# main.net
KiCad netlist of a schematic drawn in EAGLE
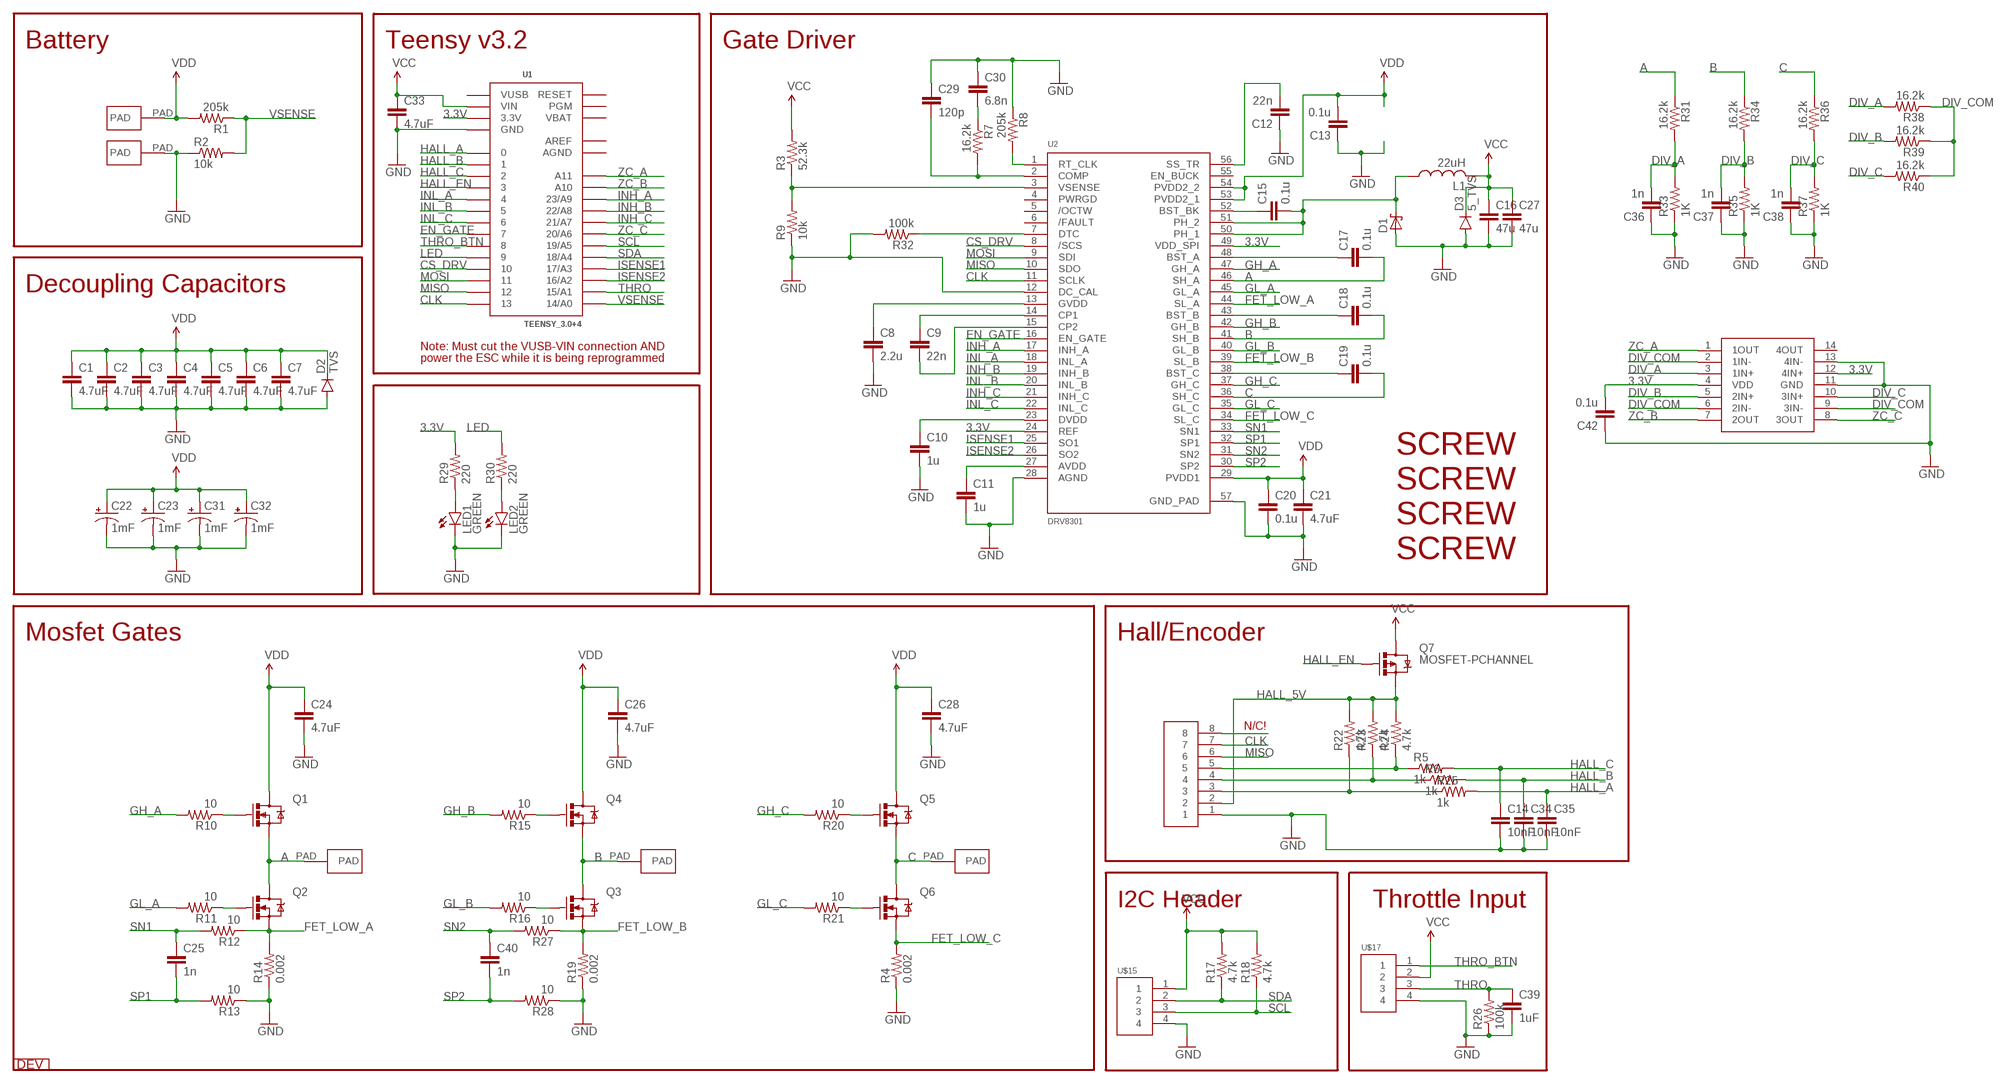
[diagram p0: schematic, sheet 1]

(export (version "E")
  (design (tool "Eeschema 10.0.6"))
  (components
    (comp (ref "C1")
      (value "4.7uF")
      (footprint "eagle-import:1206")
      (libsource (lib "eagle-import") (part "CAP1206"))
    )
    (comp (ref "C2")
      (value "4.7uF")
      (footprint "eagle-import:1206")
      (libsource (lib "eagle-import") (part "CAP1206"))
    )
    (comp (ref "C3")
      (value "4.7uF")
      (footprint "eagle-import:1206")
      (libsource (lib "eagle-import") (part "CAP1206"))
    )
    (comp (ref "C4")
      (value "4.7uF")
      (footprint "eagle-import:1206")
      (libsource (lib "eagle-import") (part "CAP1206"))
    )
    (comp (ref "C5")
      (value "4.7uF")
      (footprint "eagle-import:1206")
      (libsource (lib "eagle-import") (part "CAP1206"))
    )
    (comp (ref "C6")
      (value "4.7uF")
      (footprint "eagle-import:1206")
      (libsource (lib "eagle-import") (part "CAP1206"))
    )
    (comp (ref "C7")
      (value "4.7uF")
      (footprint "eagle-import:1206")
      (libsource (lib "eagle-import") (part "CAP1206"))
    )
    (comp (ref "C8")
      (value "2.2u")
      (footprint "eagle-import:0603-CAP")
      (libsource (lib "eagle-import") (part "CAP0603-CAP"))
    )
    (comp (ref "C9")
      (value "22n")
      (footprint "eagle-import:0603-CAP")
      (libsource (lib "eagle-import") (part "CAP0603-CAP"))
    )
    (comp (ref "C10")
      (value "1u")
      (footprint "eagle-import:0603-CAP")
      (libsource (lib "eagle-import") (part "CAP0603-CAP"))
    )
    (comp (ref "C11")
      (value "1u")
      (footprint "eagle-import:0603-CAP")
      (libsource (lib "eagle-import") (part "CAP0603-CAP"))
    )
    (comp (ref "C12")
      (value "22n")
      (footprint "eagle-import:0603-CAP")
      (libsource (lib "eagle-import") (part "CAP0603-CAP"))
    )
    (comp (ref "C13")
      (value "0.1u")
      (footprint "eagle-import:0603-CAP")
      (libsource (lib "eagle-import") (part "CAP0603-CAP"))
    )
    (comp (ref "C14")
      (value "10nF")
      (footprint "eagle-import:0603-CAP")
      (libsource (lib "eagle-import") (part "SparkFun-Passives_CAP0603-CAP"))
    )
    (comp (ref "C15")
      (value "0.1u")
      (footprint "eagle-import:0603-CAP")
      (libsource (lib "eagle-import") (part "CAP0603-CAP"))
    )
    (comp (ref "C16")
      (value "47u")
      (footprint "eagle-import:0805")
      (libsource (lib "eagle-import") (part "CAP0805"))
    )
    (comp (ref "C17")
      (value "0.1u")
      (footprint "eagle-import:0603-CAP")
      (libsource (lib "eagle-import") (part "CAP0603-CAP"))
    )
    (comp (ref "C18")
      (value "0.1u")
      (footprint "eagle-import:0603-CAP")
      (libsource (lib "eagle-import") (part "CAP0603-CAP"))
    )
    (comp (ref "C19")
      (value "0.1u")
      (footprint "eagle-import:0603-CAP")
      (libsource (lib "eagle-import") (part "CAP0603-CAP"))
    )
    (comp (ref "C20")
      (value "0.1u")
      (footprint "eagle-import:0603-CAP")
      (libsource (lib "eagle-import") (part "CAP0603-CAP"))
    )
    (comp (ref "C21")
      (value "4.7uF")
      (footprint "eagle-import:1206")
      (libsource (lib "eagle-import") (part "CAP1206"))
    )
    (comp (ref "C22")
      (value "1mF")
      (footprint "eagle-import:CPOL-RADIAL-1000UF-25V")
      (libsource (lib "eagle-import") (part "CAP_POLPTH4"))
    )
    (comp (ref "C23")
      (value "1mF")
      (footprint "eagle-import:CPOL-RADIAL-1000UF-25V")
      (libsource (lib "eagle-import") (part "CAP_POLPTH4"))
    )
    (comp (ref "C24")
      (value "4.7uF")
      (footprint "eagle-import:1206")
      (libsource (lib "eagle-import") (part "CAP1206"))
    )
    (comp (ref "C25")
      (value "1n")
      (footprint "eagle-import:0603-CAP")
      (libsource (lib "eagle-import") (part "CAP0603-CAP"))
    )
    (comp (ref "C26")
      (value "4.7uF")
      (footprint "eagle-import:1206")
      (libsource (lib "eagle-import") (part "CAP1206"))
    )
    (comp (ref "C27")
      (value "47u")
      (footprint "eagle-import:0805")
      (libsource (lib "eagle-import") (part "CAP0805"))
    )
    (comp (ref "C28")
      (value "4.7uF")
      (footprint "eagle-import:1206")
      (libsource (lib "eagle-import") (part "CAP1206"))
    )
    (comp (ref "C29")
      (value "120p")
      (footprint "eagle-import:0603-CAP")
      (libsource (lib "eagle-import") (part "CAP0603-CAP"))
    )
    (comp (ref "C30")
      (value "6.8n")
      (footprint "eagle-import:0603-CAP")
      (libsource (lib "eagle-import") (part "CAP0603-CAP"))
    )
    (comp (ref "C31")
      (value "1mF")
      (footprint "eagle-import:CPOL-RADIAL-1000UF-25V")
      (libsource (lib "eagle-import") (part "CAP_POLPTH4"))
    )
    (comp (ref "C32")
      (value "1mF")
      (footprint "eagle-import:CPOL-RADIAL-1000UF-25V")
      (libsource (lib "eagle-import") (part "CAP_POLPTH4"))
    )
    (comp (ref "C33")
      (value "4.7uF")
      (footprint "eagle-import:1206")
      (libsource (lib "eagle-import") (part "CAP1206"))
    )
    (comp (ref "C34")
      (value "10nF")
      (footprint "eagle-import:0603-CAP")
      (libsource (lib "eagle-import") (part "SparkFun-Passives_CAP0603-CAP"))
    )
    (comp (ref "C35")
      (value "10nF")
      (footprint "eagle-import:0603-CAP")
      (libsource (lib "eagle-import") (part "SparkFun-Passives_CAP0603-CAP"))
    )
    (comp (ref "C36")
      (value "1n")
      (footprint "eagle-import:0603-CAP")
      (libsource (lib "eagle-import") (part "CAP0603-CAP"))
    )
    (comp (ref "C37")
      (value "1n")
      (footprint "eagle-import:0603-CAP")
      (libsource (lib "eagle-import") (part "CAP0603-CAP"))
    )
    (comp (ref "C38")
      (value "1n")
      (footprint "eagle-import:0603-CAP")
      (libsource (lib "eagle-import") (part "CAP0603-CAP"))
    )
    (comp (ref "C39")
      (value "1uF")
      (footprint "eagle-import:0603-CAP")
      (libsource (lib "eagle-import") (part "SparkFun-Passives_CAP0603-CAP"))
    )
    (comp (ref "C40")
      (value "1n")
      (footprint "eagle-import:0603-CAP")
      (libsource (lib "eagle-import") (part "CAP0603-CAP"))
    )
    (comp (ref "C42")
      (value "0.1u")
      (footprint "eagle-import:0603-CAP")
      (libsource (lib "eagle-import") (part "CAP0603-CAP"))
    )
    (comp (ref "D1")
      (value "SCHOTTKY_SMA")
      (footprint "eagle-import:SMA")
      (libsource (lib "eagle-import") (part "SCHOTTKY_SMA"))
    )
    (comp (ref "D2")
      (value "TVS")
      (footprint "eagle-import:SMC")
      (libsource (lib "eagle-import") (part "DIODEES3J"))
    )
    (comp (ref "D3")
      (value "5_TVS")
      (footprint "eagle-import:SOT23-3")
      (libsource (lib "eagle-import") (part "DIODESOT23"))
    )
    (comp (ref "L1")
      (value "22uH")
      (footprint "eagle-import:L5650M")
      (libsource (lib "eagle-import") (part "L-USL5650M"))
    )
    (comp (ref "LED1")
      (value "GREEN")
      (footprint "eagle-import:LED-1206")
      (libsource (lib "eagle-import") (part "LED1206"))
    )
    (comp (ref "LED2")
      (value "GREEN")
      (footprint "eagle-import:LED-1206")
      (libsource (lib "eagle-import") (part "LED1206"))
    )
    (comp (ref "Q1")
      (value "MOSFET-NCHANNELDFN5X6")
      (footprint "eagle-import:DFN5X6")
      (libsource (lib "eagle-import") (part "MOSFET-NCHANNELDFN5X6"))
    )
    (comp (ref "Q2")
      (value "MOSFET-NCHANNELDFN5X6")
      (footprint "eagle-import:DFN5X6")
      (libsource (lib "eagle-import") (part "MOSFET-NCHANNELDFN5X6"))
    )
    (comp (ref "Q3")
      (value "MOSFET-NCHANNELDFN5X6")
      (footprint "eagle-import:DFN5X6")
      (libsource (lib "eagle-import") (part "MOSFET-NCHANNELDFN5X6"))
    )
    (comp (ref "Q4")
      (value "MOSFET-NCHANNELDFN5X6")
      (footprint "eagle-import:DFN5X6")
      (libsource (lib "eagle-import") (part "MOSFET-NCHANNELDFN5X6"))
    )
    (comp (ref "Q5")
      (value "MOSFET-NCHANNELDFN5X6")
      (footprint "eagle-import:DFN5X6")
      (libsource (lib "eagle-import") (part "MOSFET-NCHANNELDFN5X6"))
    )
    (comp (ref "Q6")
      (value "MOSFET-NCHANNELDFN5X6")
      (footprint "eagle-import:DFN5X6")
      (libsource (lib "eagle-import") (part "MOSFET-NCHANNELDFN5X6"))
    )
    (comp (ref "Q7")
      (value "MOSFET-PCHANNEL")
      (footprint "eagle-import:SOT23-3")
      (libsource (lib "eagle-import") (part "MOSFET-PCHANNEL"))
    )
    (comp (ref "R1")
      (value "205k")
      (footprint "eagle-import:0603-RES")
      (libsource (lib "eagle-import") (part "RESISTOR0603"))
    )
    (comp (ref "R2")
      (value "10k")
      (footprint "eagle-import:0603-RES")
      (libsource (lib "eagle-import") (part "RESISTOR0603"))
    )
    (comp (ref "R3")
      (value "52.3k")
      (footprint "eagle-import:0603-RES")
      (libsource (lib "eagle-import") (part "RESISTOR0603"))
    )
    (comp (ref "R4")
      (value "0.002")
      (footprint "eagle-import:R2512")
      (libsource (lib "eagle-import") (part "SparkFun-Resistors_RESISTOR2512"))
    )
    (comp (ref "R5")
      (value "1k")
      (footprint "eagle-import:0603-RES")
      (libsource (lib "eagle-import") (part "RESISTOR0603-RES"))
    )
    (comp (ref "R6")
      (value "1k")
      (footprint "eagle-import:0603-RES")
      (libsource (lib "eagle-import") (part "RESISTOR0603-RES"))
    )
    (comp (ref "R7")
      (value "16.2k")
      (footprint "eagle-import:0603-RES")
      (libsource (lib "eagle-import") (part "RESISTOR0603"))
    )
    (comp (ref "R8")
      (value "205k")
      (footprint "eagle-import:0603-RES")
      (libsource (lib "eagle-import") (part "RESISTOR0603"))
    )
    (comp (ref "R9")
      (value "10k")
      (footprint "eagle-import:0603-RES")
      (libsource (lib "eagle-import") (part "RESISTOR0603"))
    )
    (comp (ref "R10")
      (value "10")
      (footprint "eagle-import:0603-RES")
      (libsource (lib "eagle-import") (part "RESISTOR0603"))
    )
    (comp (ref "R11")
      (value "10")
      (footprint "eagle-import:0603-RES")
      (libsource (lib "eagle-import") (part "RESISTOR0603"))
    )
    (comp (ref "R12")
      (value "10")
      (footprint "eagle-import:0603-RES")
      (libsource (lib "eagle-import") (part "RESISTOR0603"))
    )
    (comp (ref "R13")
      (value "10")
      (footprint "eagle-import:0603-RES")
      (libsource (lib "eagle-import") (part "RESISTOR0603"))
    )
    (comp (ref "R14")
      (value "0.002")
      (footprint "eagle-import:R2512")
      (libsource (lib "eagle-import") (part "SparkFun-Resistors_RESISTOR2512"))
    )
    (comp (ref "R15")
      (value "10")
      (footprint "eagle-import:0603-RES")
      (libsource (lib "eagle-import") (part "RESISTOR0603"))
    )
    (comp (ref "R16")
      (value "10")
      (footprint "eagle-import:0603-RES")
      (libsource (lib "eagle-import") (part "RESISTOR0603"))
    )
    (comp (ref "R17")
      (value "4.7k")
      (footprint "eagle-import:0603-RES")
      (libsource (lib "eagle-import") (part "RESISTOR0603-RES"))
    )
    (comp (ref "R18")
      (value "4.7k")
      (footprint "eagle-import:0603-RES")
      (libsource (lib "eagle-import") (part "RESISTOR0603-RES"))
    )
    (comp (ref "R19")
      (value "0.002")
      (footprint "eagle-import:R2512")
      (libsource (lib "eagle-import") (part "SparkFun-Resistors_RESISTOR2512"))
    )
    (comp (ref "R20")
      (value "10")
      (footprint "eagle-import:0603-RES")
      (libsource (lib "eagle-import") (part "RESISTOR0603"))
    )
    (comp (ref "R21")
      (value "10")
      (footprint "eagle-import:0603-RES")
      (libsource (lib "eagle-import") (part "RESISTOR0603"))
    )
    (comp (ref "R22")
      (value "4.7k")
      (footprint "eagle-import:0603-RES")
      (libsource (lib "eagle-import") (part "RESISTOR0603"))
    )
    (comp (ref "R23")
      (value "4.7k")
      (footprint "eagle-import:0603-RES")
      (libsource (lib "eagle-import") (part "RESISTOR0603"))
    )
    (comp (ref "R24")
      (value "4.7k")
      (footprint "eagle-import:0603-RES")
      (libsource (lib "eagle-import") (part "RESISTOR0603"))
    )
    (comp (ref "R25")
      (value "1k")
      (footprint "eagle-import:0603-RES")
      (libsource (lib "eagle-import") (part "RESISTOR0603-RES"))
    )
    (comp (ref "R26")
      (value "100k")
      (footprint "eagle-import:0603-RES")
      (libsource (lib "eagle-import") (part "RESISTOR0603-RES"))
    )
    (comp (ref "R27")
      (value "10")
      (footprint "eagle-import:0603-RES")
      (libsource (lib "eagle-import") (part "RESISTOR0603"))
    )
    (comp (ref "R28")
      (value "10")
      (footprint "eagle-import:0603-RES")
      (libsource (lib "eagle-import") (part "RESISTOR0603"))
    )
    (comp (ref "R29")
      (value "220")
      (footprint "eagle-import:0603-RES")
      (libsource (lib "eagle-import") (part "RESISTOR0603"))
    )
    (comp (ref "R30")
      (value "220")
      (footprint "eagle-import:0603-RES")
      (libsource (lib "eagle-import") (part "RESISTOR0603"))
    )
    (comp (ref "R31")
      (value "16.2k")
      (footprint "eagle-import:0603-RES")
      (libsource (lib "eagle-import") (part "RESISTOR0603"))
    )
    (comp (ref "R32")
      (value "100k")
      (footprint "eagle-import:0603-RES")
      (libsource (lib "eagle-import") (part "RESISTOR0603"))
    )
    (comp (ref "R33")
      (value "1K")
      (footprint "eagle-import:0603-RES")
      (libsource (lib "eagle-import") (part "RESISTOR0603"))
    )
    (comp (ref "R34")
      (value "16.2k")
      (footprint "eagle-import:0603-RES")
      (libsource (lib "eagle-import") (part "RESISTOR0603"))
    )
    (comp (ref "R35")
      (value "1K")
      (footprint "eagle-import:0603-RES")
      (libsource (lib "eagle-import") (part "RESISTOR0603"))
    )
    (comp (ref "R36")
      (value "16.2k")
      (footprint "eagle-import:0603-RES")
      (libsource (lib "eagle-import") (part "RESISTOR0603"))
    )
    (comp (ref "R37")
      (value "1K")
      (footprint "eagle-import:0603-RES")
      (libsource (lib "eagle-import") (part "RESISTOR0603"))
    )
    (comp (ref "R38")
      (value "16.2k")
      (footprint "eagle-import:0603-RES")
      (libsource (lib "eagle-import") (part "RESISTOR0603"))
    )
    (comp (ref "R39")
      (value "16.2k")
      (footprint "eagle-import:0603-RES")
      (libsource (lib "eagle-import") (part "RESISTOR0603"))
    )
    (comp (ref "R40")
      (value "16.2k")
      (footprint "eagle-import:0603-RES")
      (libsource (lib "eagle-import") (part "RESISTOR0603"))
    )
    (comp (ref "U$2")
      (value "HEADER8")
      (footprint "eagle-import:8PINVALULOK")
      (libsource (lib "eagle-import") (part "HEADER8"))
    )
    (comp (ref "U$12")
      (value "OPAMP_QUAD")
      (footprint "eagle-import:TSSOP-14")
      (libsource (lib "eagle-import") (part "OPAMP_QUAD"))
    )
    (comp (ref "U$15")
      (value "HEADER4VALULOK")
      (footprint "eagle-import:4PINVALULOK")
      (libsource (lib "eagle-import") (part "HEADER4VALULOK"))
    )
    (comp (ref "U$16")
      (value "DEV")
      (footprint "eagle-import:DEV")
      (libsource (lib "eagle-import") (part "DEV"))
    )
    (comp (ref "U$17")
      (value "HEADER4VALULOK")
      (footprint "eagle-import:4PINVALULOK")
      (libsource (lib "eagle-import") (part "HEADER4VALULOK"))
    )
    (comp (ref "U$19")
      (value "SCREW")
      (footprint "eagle-import:M3HOLE")
      (libsource (lib "eagle-import") (part "SCREW"))
    )
    (comp (ref "U$20")
      (value "SCREW")
      (footprint "eagle-import:M3HOLE")
      (libsource (lib "eagle-import") (part "SCREW"))
    )
    (comp (ref "U$21")
      (value "SCREW")
      (footprint "eagle-import:M3HOLE")
      (libsource (lib "eagle-import") (part "SCREW"))
    )
    (comp (ref "U$22")
      (value "SCREW")
      (footprint "eagle-import:M3HOLE")
      (libsource (lib "eagle-import") (part "SCREW"))
    )
    (comp (ref "U$23")
      (value "PAD")
      (footprint "eagle-import:PAD")
      (libsource (lib "eagle-import") (part "PAD"))
    )
    (comp (ref "U$24")
      (value "PAD")
      (footprint "eagle-import:PAD")
      (libsource (lib "eagle-import") (part "PAD"))
    )
    (comp (ref "U$25")
      (value "PAD")
      (footprint "eagle-import:PAD")
      (libsource (lib "eagle-import") (part "PAD"))
    )
    (comp (ref "U$26")
      (value "PAD")
      (footprint "eagle-import:PAD")
      (libsource (lib "eagle-import") (part "PAD"))
    )
    (comp (ref "U$27")
      (value "PAD")
      (footprint "eagle-import:PAD")
      (libsource (lib "eagle-import") (part "PAD"))
    )
    (comp (ref "U1")
      (value "TEENSY_3.0+4")
      (footprint "eagle-import:TEENSY_3.0+4")
      (libsource (lib "eagle-import") (part "TEENSY_3.0+4"))
    )
    (comp (ref "U2")
      (value "DRV8301")
      (footprint "eagle-import:DRV8301")
      (libsource (lib "eagle-import") (part "DRV8301"))
    )
  )
  (nets
    (net (code "1") (name "/3.3V") (class "Default")
      (node (ref "C42") (pin "2") (pinfunction "2_2") (pintype "passive"))
      (node (ref "R29") (pin "2") (pinfunction "2_2") (pintype "passive"))
      (node (ref "U$12") (pin "12") (pinfunction "4IN+_12") (pintype "bidirectional"))
      (node (ref "U$12") (pin "4") (pinfunction "VDD_4") (pintype "bidirectional"))
      (node (ref "U1") (pin "3.3V") (pinfunction "3.3V_3.3V") (pintype "power_in"))
      (node (ref "U1") (pin "3.3V1") (pinfunction "3.3V_3.3V1") (pintype "power_in"))
      (node (ref "U2") (pin "24") (pinfunction "REF_24") (pintype "bidirectional"))
      (node (ref "U2") (pin "49") (pinfunction "VDD_SPI_49") (pintype "bidirectional"))
    )
    (net (code "2") (name "/A") (class "Default")
      (node (ref "C17") (pin "2") (pinfunction "2_2") (pintype "passive"))
      (node (ref "Q1") (pin "1") (pinfunction "S_1") (pintype "passive"))
      (node (ref "Q1") (pin "2") (pinfunction "S_2") (pintype "passive"))
      (node (ref "Q1") (pin "3") (pinfunction "S_3") (pintype "passive"))
      (node (ref "Q2") (pin "PAD") (pinfunction "D_PAD") (pintype "passive"))
      (node (ref "R31") (pin "1") (pinfunction "1_1") (pintype "passive"))
      (node (ref "U$23") (pin "PAD") (pinfunction "PAD_PAD") (pintype "bidirectional"))
      (node (ref "U2") (pin "46") (pinfunction "SH_A_46") (pintype "bidirectional"))
    )
    (net (code "3") (name "/AGND") (class "Default")
      (node (ref "U1") (pin "AGND") (pinfunction "AGND_AGND") (pintype "power_in"))
    )
    (net (code "4") (name "/AREF") (class "Default")
      (node (ref "U1") (pin "AREF") (pinfunction "AREF_AREF") (pintype "power_in"))
    )
    (net (code "5") (name "/B") (class "Default")
      (node (ref "C18") (pin "2") (pinfunction "2_2") (pintype "passive"))
      (node (ref "Q3") (pin "PAD") (pinfunction "D_PAD") (pintype "passive"))
      (node (ref "Q4") (pin "1") (pinfunction "S_1") (pintype "passive"))
      (node (ref "Q4") (pin "2") (pinfunction "S_2") (pintype "passive"))
      (node (ref "Q4") (pin "3") (pinfunction "S_3") (pintype "passive"))
      (node (ref "R34") (pin "1") (pinfunction "1_1") (pintype "passive"))
      (node (ref "U$24") (pin "PAD") (pinfunction "PAD_PAD") (pintype "bidirectional"))
      (node (ref "U2") (pin "41") (pinfunction "SH_B_41") (pintype "bidirectional"))
    )
    (net (code "6") (name "/C") (class "Default")
      (node (ref "C19") (pin "2") (pinfunction "2_2") (pintype "passive"))
      (node (ref "Q5") (pin "1") (pinfunction "S_1") (pintype "passive"))
      (node (ref "Q5") (pin "2") (pinfunction "S_2") (pintype "passive"))
      (node (ref "Q5") (pin "3") (pinfunction "S_3") (pintype "passive"))
      (node (ref "Q6") (pin "PAD") (pinfunction "D_PAD") (pintype "passive"))
      (node (ref "R36") (pin "1") (pinfunction "1_1") (pintype "passive"))
      (node (ref "U$25") (pin "PAD") (pinfunction "PAD_PAD") (pintype "bidirectional"))
      (node (ref "U2") (pin "36") (pinfunction "SH_C_36") (pintype "bidirectional"))
    )
    (net (code "7") (name "/CLK") (class "Default")
      (node (ref "U$2") (pin "7") (pinfunction "7_7") (pintype "bidirectional"))
      (node (ref "U1") (pin "13") (pinfunction "13_13") (pintype "bidirectional"))
      (node (ref "U2") (pin "11") (pinfunction "SCLK_11") (pintype "bidirectional"))
    )
    (net (code "8") (name "/CS_DRV") (class "Default")
      (node (ref "U1") (pin "10") (pinfunction "10_10") (pintype "bidirectional"))
      (node (ref "U2") (pin "8") (pinfunction "/SCS_8") (pintype "bidirectional"))
    )
    (net (code "9") (name "/DIV_A") (class "Default")
      (node (ref "C36") (pin "2") (pinfunction "2_2") (pintype "passive"))
      (node (ref "R31") (pin "2") (pinfunction "2_2") (pintype "passive"))
      (node (ref "R33") (pin "2") (pinfunction "2_2") (pintype "passive"))
      (node (ref "R38") (pin "2") (pinfunction "2_2") (pintype "passive"))
      (node (ref "U$12") (pin "3") (pinfunction "1IN+_3") (pintype "bidirectional"))
    )
    (net (code "10") (name "/DIV_B") (class "Default")
      (node (ref "C37") (pin "2") (pinfunction "2_2") (pintype "passive"))
      (node (ref "R34") (pin "2") (pinfunction "2_2") (pintype "passive"))
      (node (ref "R35") (pin "2") (pinfunction "2_2") (pintype "passive"))
      (node (ref "R39") (pin "2") (pinfunction "2_2") (pintype "passive"))
      (node (ref "U$12") (pin "5") (pinfunction "2IN+_5") (pintype "bidirectional"))
    )
    (net (code "11") (name "/DIV_C") (class "Default")
      (node (ref "C38") (pin "2") (pinfunction "2_2") (pintype "passive"))
      (node (ref "R36") (pin "2") (pinfunction "2_2") (pintype "passive"))
      (node (ref "R37") (pin "2") (pinfunction "2_2") (pintype "passive"))
      (node (ref "R40") (pin "2") (pinfunction "2_2") (pintype "passive"))
      (node (ref "U$12") (pin "10") (pinfunction "3IN+_10") (pintype "bidirectional"))
    )
    (net (code "12") (name "/DIV_COM") (class "Default")
      (node (ref "R38") (pin "1") (pinfunction "1_1") (pintype "passive"))
      (node (ref "R39") (pin "1") (pinfunction "1_1") (pintype "passive"))
      (node (ref "R40") (pin "1") (pinfunction "1_1") (pintype "passive"))
      (node (ref "U$12") (pin "2") (pinfunction "1IN-_2") (pintype "bidirectional"))
      (node (ref "U$12") (pin "6") (pinfunction "2IN-_6") (pintype "bidirectional"))
      (node (ref "U$12") (pin "9") (pinfunction "3IN-_9") (pintype "bidirectional"))
    )
    (net (code "13") (name "/EN_GATE") (class "Default")
      (node (ref "U1") (pin "7") (pinfunction "7_7") (pintype "bidirectional"))
      (node (ref "U2") (pin "16") (pinfunction "EN_GATE_16") (pintype "bidirectional"))
    )
    (net (code "14") (name "/FET_LOW_A") (class "Default")
      (node (ref "Q2") (pin "1") (pinfunction "S_1") (pintype "passive"))
      (node (ref "Q2") (pin "2") (pinfunction "S_2") (pintype "passive"))
      (node (ref "Q2") (pin "3") (pinfunction "S_3") (pintype "passive"))
      (node (ref "R12") (pin "1") (pinfunction "1_1") (pintype "passive"))
      (node (ref "R14") (pin "2") (pinfunction "2_2") (pintype "passive"))
      (node (ref "U2") (pin "44") (pinfunction "SL_A_44") (pintype "bidirectional"))
    )
    (net (code "15") (name "/FET_LOW_B") (class "Default")
      (node (ref "Q3") (pin "1") (pinfunction "S_1") (pintype "passive"))
      (node (ref "Q3") (pin "2") (pinfunction "S_2") (pintype "passive"))
      (node (ref "Q3") (pin "3") (pinfunction "S_3") (pintype "passive"))
      (node (ref "R19") (pin "2") (pinfunction "2_2") (pintype "passive"))
      (node (ref "R27") (pin "1") (pinfunction "1_1") (pintype "passive"))
      (node (ref "U2") (pin "39") (pinfunction "SL_B_39") (pintype "bidirectional"))
    )
    (net (code "16") (name "/FET_LOW_C") (class "Default")
      (node (ref "Q6") (pin "1") (pinfunction "S_1") (pintype "passive"))
      (node (ref "Q6") (pin "2") (pinfunction "S_2") (pintype "passive"))
      (node (ref "Q6") (pin "3") (pinfunction "S_3") (pintype "passive"))
      (node (ref "R4") (pin "2") (pinfunction "2_2") (pintype "passive"))
      (node (ref "U2") (pin "34") (pinfunction "SL_C_34") (pintype "bidirectional"))
    )
    (net (code "17") (name "/GH_A") (class "Default")
      (node (ref "R10") (pin "2") (pinfunction "2_2") (pintype "passive"))
      (node (ref "U2") (pin "47") (pinfunction "GH_A_47") (pintype "bidirectional"))
    )
    (net (code "18") (name "/GH_B") (class "Default")
      (node (ref "R15") (pin "2") (pinfunction "2_2") (pintype "passive"))
      (node (ref "U2") (pin "42") (pinfunction "GH_B_42") (pintype "bidirectional"))
    )
    (net (code "19") (name "/GH_C") (class "Default")
      (node (ref "R20") (pin "2") (pinfunction "2_2") (pintype "passive"))
      (node (ref "U2") (pin "37") (pinfunction "GH_C_37") (pintype "bidirectional"))
    )
    (net (code "20") (name "/GL_A") (class "Default")
      (node (ref "R11") (pin "2") (pinfunction "2_2") (pintype "passive"))
      (node (ref "U2") (pin "45") (pinfunction "GL_A_45") (pintype "bidirectional"))
    )
    (net (code "21") (name "/GL_B") (class "Default")
      (node (ref "R16") (pin "2") (pinfunction "2_2") (pintype "passive"))
      (node (ref "U2") (pin "40") (pinfunction "GL_B_40") (pintype "bidirectional"))
    )
    (net (code "22") (name "/GL_C") (class "Default")
      (node (ref "R21") (pin "2") (pinfunction "2_2") (pintype "passive"))
      (node (ref "U2") (pin "35") (pinfunction "GL_C_35") (pintype "bidirectional"))
    )
    (net (code "23") (name "/HALL_5V") (class "Default")
      (node (ref "Q7") (pin "2") (pinfunction "S_2") (pintype "passive"))
      (node (ref "R22") (pin "2") (pinfunction "2_2") (pintype "passive"))
      (node (ref "R23") (pin "2") (pinfunction "2_2") (pintype "passive"))
      (node (ref "R24") (pin "2") (pinfunction "2_2") (pintype "passive"))
      (node (ref "U$2") (pin "2") (pinfunction "2_2") (pintype "bidirectional"))
    )
    (net (code "24") (name "/HALL_A") (class "Default")
      (node (ref "C35") (pin "1") (pinfunction "1_1") (pintype "passive"))
      (node (ref "R25") (pin "2") (pinfunction "2_2") (pintype "passive"))
      (node (ref "U1") (pin "0") (pinfunction "0_0") (pintype "bidirectional"))
    )
    (net (code "25") (name "/HALL_B") (class "Default")
      (node (ref "C34") (pin "1") (pinfunction "1_1") (pintype "passive"))
      (node (ref "R6") (pin "2") (pinfunction "2_2") (pintype "passive"))
      (node (ref "U1") (pin "1") (pinfunction "1_1") (pintype "bidirectional"))
    )
    (net (code "26") (name "/HALL_C") (class "Default")
      (node (ref "C14") (pin "1") (pinfunction "1_1") (pintype "passive"))
      (node (ref "R5") (pin "2") (pinfunction "2_2") (pintype "passive"))
      (node (ref "U1") (pin "2") (pinfunction "2_2") (pintype "bidirectional"))
    )
    (net (code "27") (name "/HALL_EN") (class "Default")
      (node (ref "Q7") (pin "1") (pinfunction "G_1") (pintype "passive"))
      (node (ref "U1") (pin "3") (pinfunction "3_3") (pintype "bidirectional"))
    )
    (net (code "28") (name "/INH_A") (class "Default")
      (node (ref "U1") (pin "23/A9") (pinfunction "23/A9_23/A9") (pintype "bidirectional"))
      (node (ref "U2") (pin "17") (pinfunction "INH_A_17") (pintype "bidirectional"))
    )
    (net (code "29") (name "/INH_B") (class "Default")
      (node (ref "U1") (pin "22/A8") (pinfunction "22/A8_22/A8") (pintype "bidirectional"))
      (node (ref "U2") (pin "19") (pinfunction "INH_B_19") (pintype "bidirectional"))
    )
    (net (code "30") (name "/INH_C") (class "Default")
      (node (ref "U1") (pin "21/A7") (pinfunction "21/A7_21/A7") (pintype "bidirectional"))
      (node (ref "U2") (pin "21") (pinfunction "INH_C_21") (pintype "bidirectional"))
    )
    (net (code "31") (name "/INL_A") (class "Default")
      (node (ref "U1") (pin "4") (pinfunction "4_4") (pintype "bidirectional"))
      (node (ref "U2") (pin "18") (pinfunction "INL_A_18") (pintype "bidirectional"))
    )
    (net (code "32") (name "/INL_B") (class "Default")
      (node (ref "U1") (pin "5") (pinfunction "5_5") (pintype "bidirectional"))
      (node (ref "U2") (pin "20") (pinfunction "INL_B_20") (pintype "bidirectional"))
    )
    (net (code "33") (name "/INL_C") (class "Default")
      (node (ref "U1") (pin "6") (pinfunction "6_6") (pintype "bidirectional"))
      (node (ref "U2") (pin "22") (pinfunction "INL_C_22") (pintype "bidirectional"))
    )
    (net (code "34") (name "/ISENSE1") (class "Default")
      (node (ref "U1") (pin "17/A3") (pinfunction "17/A3_17/A3") (pintype "bidirectional"))
      (node (ref "U2") (pin "25") (pinfunction "SO1_25") (pintype "bidirectional"))
    )
    (net (code "35") (name "/ISENSE2") (class "Default")
      (node (ref "U1") (pin "16/A2") (pinfunction "16/A2_16/A2") (pintype "bidirectional"))
      (node (ref "U2") (pin "26") (pinfunction "SO2_26") (pintype "bidirectional"))
    )
    (net (code "36") (name "/LED") (class "Default")
      (node (ref "R30") (pin "2") (pinfunction "2_2") (pintype "passive"))
      (node (ref "U1") (pin "9") (pinfunction "9_9") (pintype "bidirectional"))
    )
    (net (code "37") (name "/MISO") (class "Default")
      (node (ref "U$2") (pin "6") (pinfunction "6_6") (pintype "bidirectional"))
      (node (ref "U1") (pin "12") (pinfunction "12_12") (pintype "bidirectional"))
      (node (ref "U2") (pin "10") (pinfunction "SDO_10") (pintype "bidirectional"))
    )
    (net (code "38") (name "/MOSI") (class "Default")
      (node (ref "U1") (pin "11") (pinfunction "11_11") (pintype "bidirectional"))
      (node (ref "U2") (pin "9") (pinfunction "SDI_9") (pintype "bidirectional"))
    )
    (net (code "39") (name "/SCL") (class "Default")
      (node (ref "R18") (pin "1") (pinfunction "1_1") (pintype "passive"))
      (node (ref "U$15") (pin "3") (pinfunction "3_3") (pintype "bidirectional"))
      (node (ref "U1") (pin "19/A5") (pinfunction "19/A5_19/A5") (pintype "bidirectional"))
    )
    (net (code "40") (name "/SDA") (class "Default")
      (node (ref "R17") (pin "1") (pinfunction "1_1") (pintype "passive"))
      (node (ref "U$15") (pin "2") (pinfunction "2_2") (pintype "bidirectional"))
      (node (ref "U1") (pin "18/A4") (pinfunction "18/A4_18/A4") (pintype "bidirectional"))
    )
    (net (code "41") (name "/SN1") (class "Default")
      (node (ref "C25") (pin "1") (pinfunction "1_1") (pintype "passive"))
      (node (ref "R12") (pin "2") (pinfunction "2_2") (pintype "passive"))
      (node (ref "U2") (pin "33") (pinfunction "SN1_33") (pintype "bidirectional"))
    )
    (net (code "42") (name "/SN2") (class "Default")
      (node (ref "C40") (pin "1") (pinfunction "1_1") (pintype "passive"))
      (node (ref "R27") (pin "2") (pinfunction "2_2") (pintype "passive"))
      (node (ref "U2") (pin "31") (pinfunction "SN2_31") (pintype "bidirectional"))
    )
    (net (code "43") (name "/SP1") (class "Default")
      (node (ref "C25") (pin "2") (pinfunction "2_2") (pintype "passive"))
      (node (ref "R13") (pin "2") (pinfunction "2_2") (pintype "passive"))
      (node (ref "U2") (pin "32") (pinfunction "SP1_32") (pintype "bidirectional"))
    )
    (net (code "44") (name "/SP2") (class "Default")
      (node (ref "C40") (pin "2") (pinfunction "2_2") (pintype "passive"))
      (node (ref "R28") (pin "2") (pinfunction "2_2") (pintype "passive"))
      (node (ref "U2") (pin "30") (pinfunction "SP2_30") (pintype "bidirectional"))
    )
    (net (code "45") (name "/THRO") (class "Default")
      (node (ref "C39") (pin "1") (pinfunction "1_1") (pintype "passive"))
      (node (ref "R26") (pin "2") (pinfunction "2_2") (pintype "passive"))
      (node (ref "U$17") (pin "3") (pinfunction "3_3") (pintype "bidirectional"))
      (node (ref "U1") (pin "15/A1") (pinfunction "15/A1_15/A1") (pintype "bidirectional"))
    )
    (net (code "46") (name "/THRO_BTN") (class "Default")
      (node (ref "U$17") (pin "1") (pinfunction "1_1") (pintype "bidirectional"))
      (node (ref "U1") (pin "8") (pinfunction "8_8") (pintype "bidirectional"))
    )
    (net (code "47") (name "/VBAT") (class "Default")
      (node (ref "U1") (pin "VBAT") (pinfunction "VBAT_VBAT") (pintype "power_in"))
    )
    (net (code "48") (name "/VSENSE") (class "Default")
      (node (ref "R1") (pin "1") (pinfunction "1_1") (pintype "passive"))
      (node (ref "R2") (pin "2") (pinfunction "2_2") (pintype "passive"))
      (node (ref "U1") (pin "14/A0") (pinfunction "14/A0_14/A0") (pintype "bidirectional"))
    )
    (net (code "49") (name "/VUSB") (class "Default")
      (node (ref "U1") (pin "VUSB") (pinfunction "VUSB_VUSB") (pintype "power_in"))
    )
    (net (code "50") (name "/ZC_A") (class "Default")
      (node (ref "U$12") (pin "1") (pinfunction "1OUT_1") (pintype "bidirectional"))
      (node (ref "U1") (pin "A11") (pinfunction "A11_A11") (pintype "bidirectional"))
    )
    (net (code "51") (name "/ZC_B") (class "Default")
      (node (ref "U$12") (pin "7") (pinfunction "2OUT_7") (pintype "bidirectional"))
      (node (ref "U1") (pin "A10") (pinfunction "A10_A10") (pintype "bidirectional"))
    )
    (net (code "52") (name "/ZC_C") (class "Default")
      (node (ref "U$12") (pin "8") (pinfunction "3OUT_8") (pintype "bidirectional"))
      (node (ref "U1") (pin "20/A6") (pinfunction "20/A6_20/A6") (pintype "bidirectional"))
    )
    (net (code "53") (name "GND") (class "Default")
      (node (ref "C1") (pin "2") (pinfunction "2_2") (pintype "passive"))
      (node (ref "C10") (pin "2") (pinfunction "2_2") (pintype "passive"))
      (node (ref "C11") (pin "2") (pinfunction "2_2") (pintype "passive"))
      (node (ref "C12") (pin "1") (pinfunction "1_1") (pintype "passive"))
      (node (ref "C13") (pin "1") (pinfunction "1_1") (pintype "passive"))
      (node (ref "C14") (pin "2") (pinfunction "2_2") (pintype "passive"))
      (node (ref "C16") (pin "2") (pinfunction "2_2") (pintype "passive"))
      (node (ref "C2") (pin "2") (pinfunction "2_2") (pintype "passive"))
      (node (ref "C20") (pin "2") (pinfunction "2_2") (pintype "passive"))
      (node (ref "C21") (pin "2") (pinfunction "2_2") (pintype "passive"))
      (node (ref "C22") (pin "-") (pinfunction "-_-") (pintype "passive"))
      (node (ref "C23") (pin "-") (pinfunction "-_-") (pintype "passive"))
      (node (ref "C24") (pin "2") (pinfunction "2_2") (pintype "passive"))
      (node (ref "C26") (pin "2") (pinfunction "2_2") (pintype "passive"))
      (node (ref "C27") (pin "2") (pinfunction "2_2") (pintype "passive"))
      (node (ref "C28") (pin "2") (pinfunction "2_2") (pintype "passive"))
      (node (ref "C29") (pin "1") (pinfunction "1_1") (pintype "passive"))
      (node (ref "C3") (pin "2") (pinfunction "2_2") (pintype "passive"))
      (node (ref "C30") (pin "1") (pinfunction "1_1") (pintype "passive"))
      (node (ref "C31") (pin "-") (pinfunction "-_-") (pintype "passive"))
      (node (ref "C32") (pin "-") (pinfunction "-_-") (pintype "passive"))
      (node (ref "C33") (pin "2") (pinfunction "2_2") (pintype "passive"))
      (node (ref "C34") (pin "2") (pinfunction "2_2") (pintype "passive"))
      (node (ref "C35") (pin "2") (pinfunction "2_2") (pintype "passive"))
      (node (ref "C36") (pin "1") (pinfunction "1_1") (pintype "passive"))
      (node (ref "C37") (pin "1") (pinfunction "1_1") (pintype "passive"))
      (node (ref "C38") (pin "1") (pinfunction "1_1") (pintype "passive"))
      (node (ref "C39") (pin "2") (pinfunction "2_2") (pintype "passive"))
      (node (ref "C4") (pin "2") (pinfunction "2_2") (pintype "passive"))
      (node (ref "C42") (pin "1") (pinfunction "1_1") (pintype "passive"))
      (node (ref "C5") (pin "2") (pinfunction "2_2") (pintype "passive"))
      (node (ref "C6") (pin "2") (pinfunction "2_2") (pintype "passive"))
      (node (ref "C7") (pin "2") (pinfunction "2_2") (pintype "passive"))
      (node (ref "C8") (pin "2") (pinfunction "2_2") (pintype "passive"))
      (node (ref "D1") (pin "A") (pinfunction "A_A") (pintype "passive"))
      (node (ref "D2") (pin "A") (pinfunction "A_A") (pintype "passive"))
      (node (ref "D3") (pin "1") (pinfunction "A_1") (pintype "passive"))
      (node (ref "LED1") (pin "C") (pinfunction "C_C") (pintype "passive"))
      (node (ref "LED2") (pin "C") (pinfunction "C_C") (pintype "passive"))
      (node (ref "R13") (pin "1") (pinfunction "1_1") (pintype "passive"))
      (node (ref "R14") (pin "1") (pinfunction "1_1") (pintype "passive"))
      (node (ref "R19") (pin "1") (pinfunction "1_1") (pintype "passive"))
      (node (ref "R2") (pin "1") (pinfunction "1_1") (pintype "passive"))
      (node (ref "R26") (pin "1") (pinfunction "1_1") (pintype "passive"))
      (node (ref "R28") (pin "1") (pinfunction "1_1") (pintype "passive"))
      (node (ref "R32") (pin "2") (pinfunction "2_2") (pintype "passive"))
      (node (ref "R33") (pin "1") (pinfunction "1_1") (pintype "passive"))
      (node (ref "R35") (pin "1") (pinfunction "1_1") (pintype "passive"))
      (node (ref "R37") (pin "1") (pinfunction "1_1") (pintype "passive"))
      (node (ref "R4") (pin "1") (pinfunction "1_1") (pintype "passive"))
      (node (ref "R8") (pin "1") (pinfunction "1_1") (pintype "passive"))
      (node (ref "R9") (pin "1") (pinfunction "1_1") (pintype "passive"))
      (node (ref "U$12") (pin "11") (pinfunction "GND_11") (pintype "bidirectional"))
      (node (ref "U$12") (pin "13") (pinfunction "4IN-_13") (pintype "bidirectional"))
      (node (ref "U$15") (pin "4") (pinfunction "4_4") (pintype "bidirectional"))
      (node (ref "U$17") (pin "4") (pinfunction "4_4") (pintype "bidirectional"))
      (node (ref "U$2") (pin "1") (pinfunction "1_1") (pintype "bidirectional"))
      (node (ref "U$27") (pin "PAD") (pinfunction "PAD_PAD") (pintype "bidirectional"))
      (node (ref "U1") (pin "GND") (pinfunction "GND_GND") (pintype "power_in"))
      (node (ref "U1") (pin "GND1") (pinfunction "GND_GND1") (pintype "power_in"))
      (node (ref "U2") (pin "12") (pinfunction "DC_CAL_12") (pintype "bidirectional"))
      (node (ref "U2") (pin "28") (pinfunction "AGND_28") (pintype "bidirectional"))
      (node (ref "U2") (pin "57") (pinfunction "GND_PAD_57") (pintype "bidirectional"))
    )
    (net (code "54") (name "Net-(C30-Pad2)") (class "Default")
      (node (ref "C30") (pin "2") (pinfunction "2_2") (pintype "passive"))
      (node (ref "R7") (pin "1") (pinfunction "1_1") (pintype "passive"))
    )
    (net (code "55") (name "Net-(LED1-PadA)") (class "Default")
      (node (ref "LED1") (pin "A") (pinfunction "A_A") (pintype "passive"))
      (node (ref "R29") (pin "1") (pinfunction "1_1") (pintype "passive"))
    )
    (net (code "56") (name "Net-(LED2-PadA)") (class "Default")
      (node (ref "LED2") (pin "A") (pinfunction "A_A") (pintype "passive"))
      (node (ref "R30") (pin "1") (pinfunction "1_1") (pintype "passive"))
    )
    (net (code "57") (name "Net-(Q1-G)") (class "Default")
      (node (ref "Q1") (pin "4") (pinfunction "G_4") (pintype "passive"))
      (node (ref "R10") (pin "1") (pinfunction "1_1") (pintype "passive"))
    )
    (net (code "58") (name "Net-(Q2-G)") (class "Default")
      (node (ref "Q2") (pin "4") (pinfunction "G_4") (pintype "passive"))
      (node (ref "R11") (pin "1") (pinfunction "1_1") (pintype "passive"))
    )
    (net (code "59") (name "Net-(Q3-G)") (class "Default")
      (node (ref "Q3") (pin "4") (pinfunction "G_4") (pintype "passive"))
      (node (ref "R16") (pin "1") (pinfunction "1_1") (pintype "passive"))
    )
    (net (code "60") (name "Net-(Q4-G)") (class "Default")
      (node (ref "Q4") (pin "4") (pinfunction "G_4") (pintype "passive"))
      (node (ref "R15") (pin "1") (pinfunction "1_1") (pintype "passive"))
    )
    (net (code "61") (name "Net-(Q5-G)") (class "Default")
      (node (ref "Q5") (pin "4") (pinfunction "G_4") (pintype "passive"))
      (node (ref "R20") (pin "1") (pinfunction "1_1") (pintype "passive"))
    )
    (net (code "62") (name "Net-(Q6-G)") (class "Default")
      (node (ref "Q6") (pin "4") (pinfunction "G_4") (pintype "passive"))
      (node (ref "R21") (pin "1") (pinfunction "1_1") (pintype "passive"))
    )
    (net (code "63") (name "Net-(R22-Pad1)") (class "Default")
      (node (ref "R22") (pin "1") (pinfunction "1_1") (pintype "passive"))
      (node (ref "R25") (pin "1") (pinfunction "1_1") (pintype "passive"))
      (node (ref "U$2") (pin "3") (pinfunction "3_3") (pintype "bidirectional"))
    )
    (net (code "64") (name "Net-(R23-Pad1)") (class "Default")
      (node (ref "R23") (pin "1") (pinfunction "1_1") (pintype "passive"))
      (node (ref "R6") (pin "1") (pinfunction "1_1") (pintype "passive"))
      (node (ref "U$2") (pin "4") (pinfunction "4_4") (pintype "bidirectional"))
    )
    (net (code "65") (name "Net-(R24-Pad1)") (class "Default")
      (node (ref "R24") (pin "1") (pinfunction "1_1") (pintype "passive"))
      (node (ref "R5") (pin "1") (pinfunction "1_1") (pintype "passive"))
      (node (ref "U$2") (pin "5") (pinfunction "5_5") (pintype "bidirectional"))
    )
    (net (code "66") (name "Net-(U2-AVDD)") (class "Default")
      (node (ref "C11") (pin "1") (pinfunction "1_1") (pintype "passive"))
      (node (ref "U2") (pin "27") (pinfunction "AVDD_27") (pintype "bidirectional"))
    )
    (net (code "67") (name "Net-(U2-BST_A)") (class "Default")
      (node (ref "C17") (pin "1") (pinfunction "1_1") (pintype "passive"))
      (node (ref "U2") (pin "48") (pinfunction "BST_A_48") (pintype "bidirectional"))
    )
    (net (code "68") (name "Net-(U2-BST_B)") (class "Default")
      (node (ref "C18") (pin "1") (pinfunction "1_1") (pintype "passive"))
      (node (ref "U2") (pin "43") (pinfunction "BST_B_43") (pintype "bidirectional"))
    )
    (net (code "69") (name "Net-(U2-BST_BK)") (class "Default")
      (node (ref "C15") (pin "1") (pinfunction "1_1") (pintype "passive"))
      (node (ref "U2") (pin "52") (pinfunction "BST_BK_52") (pintype "bidirectional"))
    )
    (net (code "70") (name "Net-(U2-BST_C)") (class "Default")
      (node (ref "C19") (pin "1") (pinfunction "1_1") (pintype "passive"))
      (node (ref "U2") (pin "38") (pinfunction "BST_C_38") (pintype "bidirectional"))
    )
    (net (code "71") (name "Net-(U2-COMP)") (class "Default")
      (node (ref "C29") (pin "2") (pinfunction "2_2") (pintype "passive"))
      (node (ref "R7") (pin "2") (pinfunction "2_2") (pintype "passive"))
      (node (ref "U2") (pin "2") (pinfunction "COMP_2") (pintype "bidirectional"))
    )
    (net (code "72") (name "Net-(U2-CP1)") (class "Default")
      (node (ref "C9") (pin "1") (pinfunction "1_1") (pintype "passive"))
      (node (ref "U2") (pin "14") (pinfunction "CP1_14") (pintype "bidirectional"))
    )
    (net (code "73") (name "Net-(U2-CP2)") (class "Default")
      (node (ref "C9") (pin "2") (pinfunction "2_2") (pintype "passive"))
      (node (ref "U2") (pin "15") (pinfunction "CP2_15") (pintype "bidirectional"))
    )
    (net (code "74") (name "Net-(U2-DTC)") (class "Default")
      (node (ref "R32") (pin "1") (pinfunction "1_1") (pintype "passive"))
      (node (ref "U2") (pin "7") (pinfunction "DTC_7") (pintype "bidirectional"))
    )
    (net (code "75") (name "Net-(U2-DVDD)") (class "Default")
      (node (ref "C10") (pin "1") (pinfunction "1_1") (pintype "passive"))
      (node (ref "U2") (pin "23") (pinfunction "DVDD_23") (pintype "bidirectional"))
    )
    (net (code "76") (name "Net-(U2-GVDD)") (class "Default")
      (node (ref "C8") (pin "1") (pinfunction "1_1") (pintype "passive"))
      (node (ref "U2") (pin "13") (pinfunction "GVDD_13") (pintype "bidirectional"))
    )
    (net (code "77") (name "Net-(U2-PH_1)") (class "Default")
      (node (ref "C15") (pin "2") (pinfunction "2_2") (pintype "passive"))
      (node (ref "D1") (pin "C") (pinfunction "C_C") (pintype "passive"))
      (node (ref "L1") (pin "1") (pinfunction "1_1") (pintype "passive"))
      (node (ref "U2") (pin "50") (pinfunction "PH_1_50") (pintype "bidirectional"))
      (node (ref "U2") (pin "51") (pinfunction "PH_2_51") (pintype "bidirectional"))
    )
    (net (code "78") (name "Net-(U2-RT_CLK)") (class "Default")
      (node (ref "R8") (pin "2") (pinfunction "2_2") (pintype "passive"))
      (node (ref "U2") (pin "1") (pinfunction "RT_CLK_1") (pintype "bidirectional"))
    )
    (net (code "79") (name "Net-(U2-SS_TR)") (class "Default")
      (node (ref "C12") (pin "2") (pinfunction "2_2") (pintype "passive"))
      (node (ref "U2") (pin "56") (pinfunction "SS_TR_56") (pintype "bidirectional"))
    )
    (net (code "80") (name "Net-(U2-VSENSE)") (class "Default")
      (node (ref "R3") (pin "1") (pinfunction "1_1") (pintype "passive"))
      (node (ref "R9") (pin "2") (pinfunction "2_2") (pintype "passive"))
      (node (ref "U2") (pin "3") (pinfunction "VSENSE_3") (pintype "bidirectional"))
    )
    (net (code "81") (name "VCC") (class "Default")
      (node (ref "C16") (pin "1") (pinfunction "1_1") (pintype "passive"))
      (node (ref "C27") (pin "1") (pinfunction "1_1") (pintype "passive"))
      (node (ref "C33") (pin "1") (pinfunction "1_1") (pintype "passive"))
      (node (ref "D3") (pin "3") (pinfunction "C_3") (pintype "passive"))
      (node (ref "L1") (pin "2") (pinfunction "2_2") (pintype "passive"))
      (node (ref "Q7") (pin "3") (pinfunction "D_3") (pintype "passive"))
      (node (ref "R17") (pin "2") (pinfunction "2_2") (pintype "passive"))
      (node (ref "R18") (pin "2") (pinfunction "2_2") (pintype "passive"))
      (node (ref "R3") (pin "2") (pinfunction "2_2") (pintype "passive"))
      (node (ref "U$15") (pin "1") (pinfunction "1_1") (pintype "bidirectional"))
      (node (ref "U$17") (pin "2") (pinfunction "2_2") (pintype "bidirectional"))
      (node (ref "U1") (pin "VIN") (pinfunction "VIN_VIN") (pintype "power_in"))
    )
    (net (code "82") (name "VDD") (class "Default")
      (node (ref "C1") (pin "1") (pinfunction "1_1") (pintype "passive"))
      (node (ref "C13") (pin "2") (pinfunction "2_2") (pintype "passive"))
      (node (ref "C2") (pin "1") (pinfunction "1_1") (pintype "passive"))
      (node (ref "C20") (pin "1") (pinfunction "1_1") (pintype "passive"))
      (node (ref "C21") (pin "1") (pinfunction "1_1") (pintype "passive"))
      (node (ref "C22") (pin "+") (pinfunction "+_+") (pintype "passive"))
      (node (ref "C23") (pin "+") (pinfunction "+_+") (pintype "passive"))
      (node (ref "C24") (pin "1") (pinfunction "1_1") (pintype "passive"))
      (node (ref "C26") (pin "1") (pinfunction "1_1") (pintype "passive"))
      (node (ref "C28") (pin "1") (pinfunction "1_1") (pintype "passive"))
      (node (ref "C3") (pin "1") (pinfunction "1_1") (pintype "passive"))
      (node (ref "C31") (pin "+") (pinfunction "+_+") (pintype "passive"))
      (node (ref "C32") (pin "+") (pinfunction "+_+") (pintype "passive"))
      (node (ref "C4") (pin "1") (pinfunction "1_1") (pintype "passive"))
      (node (ref "C5") (pin "1") (pinfunction "1_1") (pintype "passive"))
      (node (ref "C6") (pin "1") (pinfunction "1_1") (pintype "passive"))
      (node (ref "C7") (pin "1") (pinfunction "1_1") (pintype "passive"))
      (node (ref "D2") (pin "C") (pinfunction "C_C") (pintype "passive"))
      (node (ref "Q1") (pin "PAD") (pinfunction "D_PAD") (pintype "passive"))
      (node (ref "Q4") (pin "PAD") (pinfunction "D_PAD") (pintype "passive"))
      (node (ref "Q5") (pin "PAD") (pinfunction "D_PAD") (pintype "passive"))
      (node (ref "R1") (pin "2") (pinfunction "2_2") (pintype "passive"))
      (node (ref "U$26") (pin "PAD") (pinfunction "PAD_PAD") (pintype "bidirectional"))
      (node (ref "U2") (pin "29") (pinfunction "PVDD1_29") (pintype "bidirectional"))
      (node (ref "U2") (pin "53") (pinfunction "PVDD2_1_53") (pintype "bidirectional"))
      (node (ref "U2") (pin "54") (pinfunction "PVDD2_2_54") (pintype "bidirectional"))
    )
    (net (code "83") (name "unconnected-(U$2-Pad8)") (class "Default")
      (node (ref "U$2") (pin "8") (pinfunction "8_8") (pintype "bidirectional"))
    )
    (net (code "84") (name "unconnected-(U$12-4OUT-Pad14)") (class "Default")
      (node (ref "U$12") (pin "14") (pinfunction "4OUT_14") (pintype "bidirectional"))
    )
    (net (code "85") (name "unconnected-(U1-PadPGM)") (class "Default")
      (node (ref "U1") (pin "PGM") (pinfunction "PGM_PGM") (pintype "bidirectional"))
    )
    (net (code "86") (name "unconnected-(U1-PadRESET)") (class "Default")
      (node (ref "U1") (pin "RESET") (pinfunction "RESET_RESET") (pintype "bidirectional"))
    )
    (net (code "87") (name "unconnected-(U2-EN_BUCK-Pad55)") (class "Default")
      (node (ref "U2") (pin "55") (pinfunction "EN_BUCK_55") (pintype "bidirectional"))
    )
    (net (code "88") (name "unconnected-(U2-PWRGD-Pad4)") (class "Default")
      (node (ref "U2") (pin "4") (pinfunction "PWRGD_4") (pintype "bidirectional"))
    )
    (net (code "89") (name "unconnected-(U2-{slash}FAULT-Pad6)") (class "Default")
      (node (ref "U2") (pin "6") (pinfunction "/FAULT_6") (pintype "bidirectional"))
    )
    (net (code "90") (name "unconnected-(U2-{slash}OCTW-Pad5)") (class "Default")
      (node (ref "U2") (pin "5") (pinfunction "/OCTW_5") (pintype "bidirectional"))
    )
  )
)
